# Pro_Trinket_Keyboard_V4_1.net
KiCad netlist of a schematic drawn in EAGLE
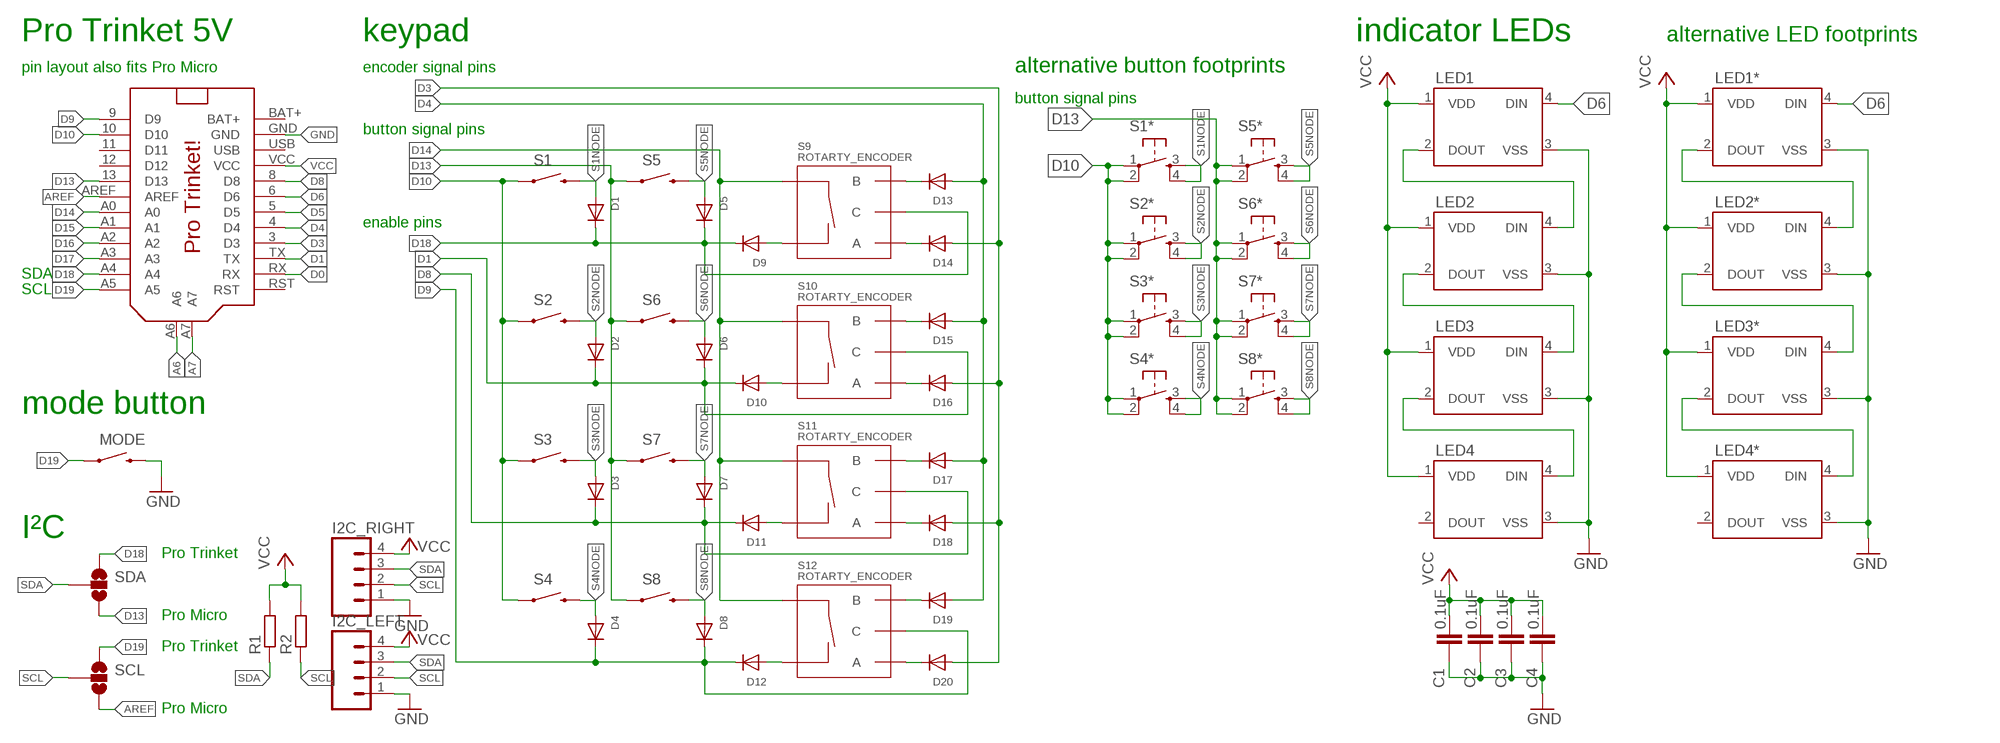
[diagram p0: schematic, sheet 1]

(export (version "E")
  (design (tool "Eeschema 10.0.6"))
  (components
    (comp (ref "C1")
      (value "0.1uF")
      (footprint "eagle-import:0603-CAP")
      (libsource (lib "eagle-import") (part "22PF-50V-5%(0603)"))
    )
    (comp (ref "C2")
      (value "0.1uF")
      (footprint "eagle-import:0603-CAP")
      (libsource (lib "eagle-import") (part "22PF-50V-5%(0603)"))
    )
    (comp (ref "C3")
      (value "0.1uF")
      (footprint "eagle-import:0603-CAP")
      (libsource (lib "eagle-import") (part "22PF-50V-5%(0603)"))
    )
    (comp (ref "C4")
      (value "0.1uF")
      (footprint "eagle-import:0603-CAP")
      (libsource (lib "eagle-import") (part "22PF-50V-5%(0603)"))
    )
    (comp (ref "D1")
      (value "DIODESOD-123")
      (footprint "eagle-import:SOD-123")
      (libsource (lib "eagle-import") (part "DIODESOD-123"))
    )
    (comp (ref "D2")
      (value "DIODESOD-123")
      (footprint "eagle-import:SOD-123")
      (libsource (lib "eagle-import") (part "DIODESOD-123"))
    )
    (comp (ref "D3")
      (value "DIODESOD-123")
      (footprint "eagle-import:SOD-123")
      (libsource (lib "eagle-import") (part "DIODESOD-123"))
    )
    (comp (ref "D4")
      (value "DIODESOD-123")
      (footprint "eagle-import:SOD-123")
      (libsource (lib "eagle-import") (part "DIODESOD-123"))
    )
    (comp (ref "D5")
      (value "DIODESOD-123")
      (footprint "eagle-import:SOD-123")
      (libsource (lib "eagle-import") (part "DIODESOD-123"))
    )
    (comp (ref "D6")
      (value "DIODESOD-123")
      (footprint "eagle-import:SOD-123")
      (libsource (lib "eagle-import") (part "DIODESOD-123"))
    )
    (comp (ref "D7")
      (value "DIODESOD-123")
      (footprint "eagle-import:SOD-123")
      (libsource (lib "eagle-import") (part "DIODESOD-123"))
    )
    (comp (ref "D8")
      (value "DIODESOD-123")
      (footprint "eagle-import:SOD-123")
      (libsource (lib "eagle-import") (part "DIODESOD-123"))
    )
    (comp (ref "D9")
      (value "DIODESOD-123")
      (footprint "eagle-import:SOD-123")
      (libsource (lib "eagle-import") (part "DIODESOD-123"))
    )
    (comp (ref "D10")
      (value "DIODESOD-123")
      (footprint "eagle-import:SOD-123")
      (libsource (lib "eagle-import") (part "DIODESOD-123"))
    )
    (comp (ref "D11")
      (value "DIODESOD-123")
      (footprint "eagle-import:SOD-123")
      (libsource (lib "eagle-import") (part "DIODESOD-123"))
    )
    (comp (ref "D12")
      (value "DIODESOD-123")
      (footprint "eagle-import:SOD-123")
      (libsource (lib "eagle-import") (part "DIODESOD-123"))
    )
    (comp (ref "D13")
      (value "DIODESOD-123")
      (footprint "eagle-import:SOD-123")
      (libsource (lib "eagle-import") (part "DIODESOD-123"))
    )
    (comp (ref "D14")
      (value "DIODESOD-123")
      (footprint "eagle-import:SOD-123")
      (libsource (lib "eagle-import") (part "DIODESOD-123"))
    )
    (comp (ref "D15")
      (value "DIODESOD-123")
      (footprint "eagle-import:SOD-123")
      (libsource (lib "eagle-import") (part "DIODESOD-123"))
    )
    (comp (ref "D16")
      (value "DIODESOD-123")
      (footprint "eagle-import:SOD-123")
      (libsource (lib "eagle-import") (part "DIODESOD-123"))
    )
    (comp (ref "D17")
      (value "DIODESOD-123")
      (footprint "eagle-import:SOD-123")
      (libsource (lib "eagle-import") (part "DIODESOD-123"))
    )
    (comp (ref "D18")
      (value "DIODESOD-123")
      (footprint "eagle-import:SOD-123")
      (libsource (lib "eagle-import") (part "DIODESOD-123"))
    )
    (comp (ref "D19")
      (value "DIODESOD-123")
      (footprint "eagle-import:SOD-123")
      (libsource (lib "eagle-import") (part "DIODESOD-123"))
    )
    (comp (ref "D20")
      (value "DIODESOD-123")
      (footprint "eagle-import:SOD-123")
      (libsource (lib "eagle-import") (part "DIODESOD-123"))
    )
    (comp (ref "I2C_LEFT")
      (value "M04PTH")
      (footprint "eagle-import:1X04")
      (libsource (lib "eagle-import") (part "M04PTH"))
    )
    (comp (ref "I2C_RIGHT")
      (value "M04PTH")
      (footprint "eagle-import:1X04")
      (libsource (lib "eagle-import") (part "M04PTH"))
    )
    (comp (ref "LED1")
      (value "WS2812B")
      (footprint "eagle-import:WS2812B")
      (libsource (lib "eagle-import") (part "WS2812B"))
    )
    (comp (ref "LED1*")
      (value "WS2812B")
      (footprint "eagle-import:WS2812B")
      (libsource (lib "eagle-import") (part "WS2812B"))
    )
    (comp (ref "LED2")
      (value "WS2812B")
      (footprint "eagle-import:WS2812B")
      (libsource (lib "eagle-import") (part "WS2812B"))
    )
    (comp (ref "LED2*")
      (value "WS2812B")
      (footprint "eagle-import:WS2812B")
      (libsource (lib "eagle-import") (part "WS2812B"))
    )
    (comp (ref "LED3")
      (value "WS2812B")
      (footprint "eagle-import:WS2812B")
      (libsource (lib "eagle-import") (part "WS2812B"))
    )
    (comp (ref "LED3*")
      (value "WS2812B")
      (footprint "eagle-import:WS2812B")
      (libsource (lib "eagle-import") (part "WS2812B"))
    )
    (comp (ref "LED4")
      (value "WS2812B")
      (footprint "eagle-import:WS2812B")
      (libsource (lib "eagle-import") (part "WS2812B"))
    )
    (comp (ref "LED4*")
      (value "WS2812B")
      (footprint "eagle-import:WS2812B")
      (libsource (lib "eagle-import") (part "WS2812B"))
    )
    (comp (ref "MODE")
      (value "SWITCH-MOMENTARY-2SIDE_EZ")
      (footprint "eagle-import:TACTILE-PTH-SIDEEZ")
      (libsource (lib "eagle-import") (part "SWITCH-MOMENTARY-2SIDE_EZ"))
    )
    (comp (ref "PRO_TRINKET")
      (value "PRO_TRINKET")
      (footprint "eagle-import:PROTRINKET")
      (libsource (lib "eagle-import") (part "PRO_TRINKET"))
    )
    (comp (ref "R1")
      (value "RESISTORR805-0805")
      (footprint "eagle-import:R805")
      (libsource (lib "eagle-import") (part "RESISTOR-0805R805"))
    )
    (comp (ref "R2")
      (value "RESISTORR805-0805")
      (footprint "eagle-import:R805")
      (libsource (lib "eagle-import") (part "RESISTOR-0805R805"))
    )
    (comp (ref "S1")
      (value "SWITCH-MOMENTARY-212MM")
      (footprint "eagle-import:TACTILE-PTH-12MM")
      (libsource (lib "eagle-import") (part "SWITCH-MOMENTARY-212MM"))
    )
    (comp (ref "S1*")
      (value "TACTILE-SWITCH-PTH")
      (footprint "eagle-import:TAC-SWITCH-PTH")
      (libsource (lib "eagle-import") (part "TACTILE-SWITCH-PTH"))
    )
    (comp (ref "S2")
      (value "SWITCH-MOMENTARY-212MM")
      (footprint "eagle-import:TACTILE-PTH-12MM")
      (libsource (lib "eagle-import") (part "SWITCH-MOMENTARY-212MM"))
    )
    (comp (ref "S2*")
      (value "TACTILE-SWITCH-PTH")
      (footprint "eagle-import:TAC-SWITCH-PTH")
      (libsource (lib "eagle-import") (part "TACTILE-SWITCH-PTH"))
    )
    (comp (ref "S3")
      (value "SWITCH-MOMENTARY-212MM")
      (footprint "eagle-import:TACTILE-PTH-12MM")
      (libsource (lib "eagle-import") (part "SWITCH-MOMENTARY-212MM"))
    )
    (comp (ref "S3*")
      (value "TACTILE-SWITCH-PTH")
      (footprint "eagle-import:TAC-SWITCH-PTH")
      (libsource (lib "eagle-import") (part "TACTILE-SWITCH-PTH"))
    )
    (comp (ref "S4")
      (value "SWITCH-MOMENTARY-212MM")
      (footprint "eagle-import:TACTILE-PTH-12MM")
      (libsource (lib "eagle-import") (part "SWITCH-MOMENTARY-212MM"))
    )
    (comp (ref "S4*")
      (value "TACTILE-SWITCH-PTH")
      (footprint "eagle-import:TAC-SWITCH-PTH")
      (libsource (lib "eagle-import") (part "TACTILE-SWITCH-PTH"))
    )
    (comp (ref "S5")
      (value "SWITCH-MOMENTARY-212MM")
      (footprint "eagle-import:TACTILE-PTH-12MM")
      (libsource (lib "eagle-import") (part "SWITCH-MOMENTARY-212MM"))
    )
    (comp (ref "S5*")
      (value "TACTILE-SWITCH-PTH")
      (footprint "eagle-import:TAC-SWITCH-PTH")
      (libsource (lib "eagle-import") (part "TACTILE-SWITCH-PTH"))
    )
    (comp (ref "S6")
      (value "SWITCH-MOMENTARY-212MM")
      (footprint "eagle-import:TACTILE-PTH-12MM")
      (libsource (lib "eagle-import") (part "SWITCH-MOMENTARY-212MM"))
    )
    (comp (ref "S6*")
      (value "TACTILE-SWITCH-PTH")
      (footprint "eagle-import:TAC-SWITCH-PTH")
      (libsource (lib "eagle-import") (part "TACTILE-SWITCH-PTH"))
    )
    (comp (ref "S7")
      (value "SWITCH-MOMENTARY-212MM")
      (footprint "eagle-import:TACTILE-PTH-12MM")
      (libsource (lib "eagle-import") (part "SWITCH-MOMENTARY-212MM"))
    )
    (comp (ref "S7*")
      (value "TACTILE-SWITCH-PTH")
      (footprint "eagle-import:TAC-SWITCH-PTH")
      (libsource (lib "eagle-import") (part "TACTILE-SWITCH-PTH"))
    )
    (comp (ref "S8")
      (value "SWITCH-MOMENTARY-212MM")
      (footprint "eagle-import:TACTILE-PTH-12MM")
      (libsource (lib "eagle-import") (part "SWITCH-MOMENTARY-212MM"))
    )
    (comp (ref "S8*")
      (value "TACTILE-SWITCH-PTH")
      (footprint "eagle-import:TAC-SWITCH-PTH")
      (libsource (lib "eagle-import") (part "TACTILE-SWITCH-PTH"))
    )
    (comp (ref "S9")
      (value "ROTARTY_ENCODER")
      (footprint "eagle-import:ROTARY_ENC_PLAIN")
      (libsource (lib "eagle-import") (part "ROTARTY_ENCODER"))
    )
    (comp (ref "S10")
      (value "ROTARTY_ENCODER")
      (footprint "eagle-import:ROTARY_ENC_PLAIN")
      (libsource (lib "eagle-import") (part "ROTARTY_ENCODER"))
    )
    (comp (ref "S11")
      (value "ROTARTY_ENCODER")
      (footprint "eagle-import:ROTARY_ENC_PLAIN")
      (libsource (lib "eagle-import") (part "ROTARTY_ENCODER"))
    )
    (comp (ref "S12")
      (value "ROTARTY_ENCODER")
      (footprint "eagle-import:ROTARY_ENC_PLAIN")
      (libsource (lib "eagle-import") (part "ROTARTY_ENCODER"))
    )
    (comp (ref "SCL")
      (value "SOLDERJUMPER_2WAYS")
      (footprint "eagle-import:SJ_3")
      (libsource (lib "eagle-import") (part "SOLDERJUMPER_2WAYS"))
    )
    (comp (ref "SDA")
      (value "SOLDERJUMPER_2WAYS")
      (footprint "eagle-import:SJ_3")
      (libsource (lib "eagle-import") (part "SOLDERJUMPER_2WAYS"))
    )
  )
  (nets
    (net (code "1") (name "/BAT+") (class "Default")
      (node (ref "PRO_TRINKET") (pin "BAT+") (pinfunction "BAT+_BAT+") (pintype "power_in"))
    )
    (net (code "2") (name "/L1NODE") (class "Default")
      (node (ref "LED1") (pin "2") (pinfunction "DOUT_2") (pintype "output"))
      (node (ref "LED1*") (pin "2") (pinfunction "DOUT_2") (pintype "output"))
      (node (ref "LED2") (pin "4") (pinfunction "DIN_4") (pintype "input"))
      (node (ref "LED2*") (pin "4") (pinfunction "DIN_4") (pintype "input"))
    )
    (net (code "3") (name "/L2NODE") (class "Default")
      (node (ref "LED2") (pin "2") (pinfunction "DOUT_2") (pintype "output"))
      (node (ref "LED2*") (pin "2") (pinfunction "DOUT_2") (pintype "output"))
      (node (ref "LED3") (pin "4") (pinfunction "DIN_4") (pintype "input"))
      (node (ref "LED3*") (pin "4") (pinfunction "DIN_4") (pintype "input"))
    )
    (net (code "4") (name "/L3NODE") (class "Default")
      (node (ref "LED3") (pin "2") (pinfunction "DOUT_2") (pintype "output"))
      (node (ref "LED3*") (pin "2") (pinfunction "DOUT_2") (pintype "output"))
      (node (ref "LED4") (pin "4") (pinfunction "DIN_4") (pintype "input"))
      (node (ref "LED4*") (pin "4") (pinfunction "DIN_4") (pintype "input"))
    )
    (net (code "5") (name "/USB") (class "Default")
      (node (ref "PRO_TRINKET") (pin "USB") (pinfunction "USB_USB") (pintype "power_in"))
    )
    (net (code "6") (name "A6") (class "Default")
      (node (ref "PRO_TRINKET") (pin "A6") (pinfunction "A6_A6") (pintype "passive"))
    )
    (net (code "7") (name "A7") (class "Default")
      (node (ref "PRO_TRINKET") (pin "A7") (pinfunction "A7_A7") (pintype "passive"))
    )
    (net (code "8") (name "AREF") (class "Default")
      (node (ref "PRO_TRINKET") (pin "AREF") (pinfunction "AREF_AREF") (pintype "passive"))
      (node (ref "SCL") (pin "3") (pinfunction "3_3") (pintype "passive"))
    )
    (net (code "9") (name "D0") (class "Default")
      (node (ref "PRO_TRINKET") (pin "RX") (pinfunction "RX_RX") (pintype "bidirectional"))
    )
    (net (code "10") (name "D1") (class "Default")
      (node (ref "D10") (pin "C") (pinfunction "C_C") (pintype "passive"))
      (node (ref "D2") (pin "C") (pinfunction "C_C") (pintype "passive"))
      (node (ref "D6") (pin "C") (pinfunction "C_C") (pintype "passive"))
      (node (ref "PRO_TRINKET") (pin "TX") (pinfunction "TX_TX") (pintype "bidirectional"))
      (node (ref "S10") (pin "C") (pinfunction "C_C") (pintype "bidirectional"))
    )
    (net (code "11") (name "D3") (class "Default")
      (node (ref "D14") (pin "A") (pinfunction "A_A") (pintype "passive"))
      (node (ref "D16") (pin "A") (pinfunction "A_A") (pintype "passive"))
      (node (ref "D18") (pin "A") (pinfunction "A_A") (pintype "passive"))
      (node (ref "D20") (pin "A") (pinfunction "A_A") (pintype "passive"))
      (node (ref "PRO_TRINKET") (pin "3") (pinfunction "D3_3") (pintype "bidirectional"))
    )
    (net (code "12") (name "D4") (class "Default")
      (node (ref "D13") (pin "A") (pinfunction "A_A") (pintype "passive"))
      (node (ref "D15") (pin "A") (pinfunction "A_A") (pintype "passive"))
      (node (ref "D17") (pin "A") (pinfunction "A_A") (pintype "passive"))
      (node (ref "D19") (pin "A") (pinfunction "A_A") (pintype "passive"))
      (node (ref "PRO_TRINKET") (pin "4") (pinfunction "D4_4") (pintype "bidirectional"))
    )
    (net (code "13") (name "D5") (class "Default")
      (node (ref "PRO_TRINKET") (pin "5") (pinfunction "D5_5") (pintype "bidirectional"))
    )
    (net (code "14") (name "D6") (class "Default")
      (node (ref "LED1") (pin "4") (pinfunction "DIN_4") (pintype "input"))
      (node (ref "LED1*") (pin "4") (pinfunction "DIN_4") (pintype "input"))
      (node (ref "PRO_TRINKET") (pin "6") (pinfunction "D6_6") (pintype "bidirectional"))
    )
    (net (code "15") (name "D8") (class "Default")
      (node (ref "D11") (pin "C") (pinfunction "C_C") (pintype "passive"))
      (node (ref "D3") (pin "C") (pinfunction "C_C") (pintype "passive"))
      (node (ref "D7") (pin "C") (pinfunction "C_C") (pintype "passive"))
      (node (ref "PRO_TRINKET") (pin "8") (pinfunction "D8_8") (pintype "bidirectional"))
      (node (ref "S11") (pin "C") (pinfunction "C_C") (pintype "bidirectional"))
    )
    (net (code "16") (name "D9") (class "Default")
      (node (ref "D12") (pin "C") (pinfunction "C_C") (pintype "passive"))
      (node (ref "D4") (pin "C") (pinfunction "C_C") (pintype "passive"))
      (node (ref "D8") (pin "C") (pinfunction "C_C") (pintype "passive"))
      (node (ref "PRO_TRINKET") (pin "9") (pinfunction "D9_9") (pintype "bidirectional"))
      (node (ref "S12") (pin "C") (pinfunction "C_C") (pintype "bidirectional"))
    )
    (net (code "17") (name "D10") (class "Default")
      (node (ref "PRO_TRINKET") (pin "10") (pinfunction "D10_10") (pintype "bidirectional"))
      (node (ref "S1") (pin "1") (pinfunction "1_1") (pintype "passive"))
      (node (ref "S1") (pin "2") (pinfunction "1_2") (pintype "passive"))
      (node (ref "S1*") (pin "1") (pinfunction "1_1") (pintype "passive"))
      (node (ref "S1*") (pin "2") (pinfunction "2_2") (pintype "passive"))
      (node (ref "S2") (pin "1") (pinfunction "1_1") (pintype "passive"))
      (node (ref "S2") (pin "2") (pinfunction "1_2") (pintype "passive"))
      (node (ref "S2*") (pin "1") (pinfunction "1_1") (pintype "passive"))
      (node (ref "S2*") (pin "2") (pinfunction "2_2") (pintype "passive"))
      (node (ref "S3") (pin "1") (pinfunction "1_1") (pintype "passive"))
      (node (ref "S3") (pin "2") (pinfunction "1_2") (pintype "passive"))
      (node (ref "S3*") (pin "1") (pinfunction "1_1") (pintype "passive"))
      (node (ref "S3*") (pin "2") (pinfunction "2_2") (pintype "passive"))
      (node (ref "S4") (pin "1") (pinfunction "1_1") (pintype "passive"))
      (node (ref "S4") (pin "2") (pinfunction "1_2") (pintype "passive"))
      (node (ref "S4*") (pin "1") (pinfunction "1_1") (pintype "passive"))
      (node (ref "S4*") (pin "2") (pinfunction "2_2") (pintype "passive"))
    )
    (net (code "18") (name "D13") (class "Default")
      (node (ref "PRO_TRINKET") (pin "13") (pinfunction "D13_13") (pintype "bidirectional"))
      (node (ref "S5") (pin "1") (pinfunction "1_1") (pintype "passive"))
      (node (ref "S5") (pin "2") (pinfunction "1_2") (pintype "passive"))
      (node (ref "S5*") (pin "1") (pinfunction "1_1") (pintype "passive"))
      (node (ref "S5*") (pin "2") (pinfunction "2_2") (pintype "passive"))
      (node (ref "S6") (pin "1") (pinfunction "1_1") (pintype "passive"))
      (node (ref "S6") (pin "2") (pinfunction "1_2") (pintype "passive"))
      (node (ref "S6*") (pin "1") (pinfunction "1_1") (pintype "passive"))
      (node (ref "S6*") (pin "2") (pinfunction "2_2") (pintype "passive"))
      (node (ref "S7") (pin "1") (pinfunction "1_1") (pintype "passive"))
      (node (ref "S7") (pin "2") (pinfunction "1_2") (pintype "passive"))
      (node (ref "S7*") (pin "1") (pinfunction "1_1") (pintype "passive"))
      (node (ref "S7*") (pin "2") (pinfunction "2_2") (pintype "passive"))
      (node (ref "S8") (pin "1") (pinfunction "1_1") (pintype "passive"))
      (node (ref "S8") (pin "2") (pinfunction "1_2") (pintype "passive"))
      (node (ref "S8*") (pin "1") (pinfunction "1_1") (pintype "passive"))
      (node (ref "S8*") (pin "2") (pinfunction "2_2") (pintype "passive"))
      (node (ref "SDA") (pin "3") (pinfunction "3_3") (pintype "passive"))
    )
    (net (code "19") (name "D14") (class "Default")
      (node (ref "PRO_TRINKET") (pin "A0") (pinfunction "A0_A0") (pintype "bidirectional"))
      (node (ref "S10") (pin "SW+") (pinfunction "SW+_SW+") (pintype "bidirectional"))
      (node (ref "S11") (pin "SW+") (pinfunction "SW+_SW+") (pintype "bidirectional"))
      (node (ref "S12") (pin "SW+") (pinfunction "SW+_SW+") (pintype "bidirectional"))
      (node (ref "S9") (pin "SW+") (pinfunction "SW+_SW+") (pintype "bidirectional"))
    )
    (net (code "20") (name "D15") (class "Default")
      (node (ref "PRO_TRINKET") (pin "A1") (pinfunction "A1_A1") (pintype "bidirectional"))
    )
    (net (code "21") (name "D16") (class "Default")
      (node (ref "PRO_TRINKET") (pin "A2") (pinfunction "A2_A2") (pintype "bidirectional"))
    )
    (net (code "22") (name "D17") (class "Default")
      (node (ref "PRO_TRINKET") (pin "A3") (pinfunction "A3_A3") (pintype "bidirectional"))
    )
    (net (code "23") (name "D18") (class "Default")
      (node (ref "D1") (pin "C") (pinfunction "C_C") (pintype "passive"))
      (node (ref "D5") (pin "C") (pinfunction "C_C") (pintype "passive"))
      (node (ref "D9") (pin "C") (pinfunction "C_C") (pintype "passive"))
      (node (ref "PRO_TRINKET") (pin "A4") (pinfunction "A4_A4") (pintype "bidirectional"))
      (node (ref "S9") (pin "C") (pinfunction "C_C") (pintype "bidirectional"))
      (node (ref "SDA") (pin "1") (pinfunction "1_1") (pintype "passive"))
    )
    (net (code "24") (name "D19") (class "Default")
      (node (ref "MODE") (pin "1") (pinfunction "1_1") (pintype "passive"))
      (node (ref "PRO_TRINKET") (pin "A5") (pinfunction "A5_A5") (pintype "bidirectional"))
      (node (ref "SCL") (pin "1") (pinfunction "1_1") (pintype "passive"))
    )
    (net (code "25") (name "GND") (class "Default")
      (node (ref "C1") (pin "1") (pinfunction "1_1") (pintype "passive"))
      (node (ref "C2") (pin "1") (pinfunction "1_1") (pintype "passive"))
      (node (ref "C3") (pin "1") (pinfunction "1_1") (pintype "passive"))
      (node (ref "C4") (pin "1") (pinfunction "1_1") (pintype "passive"))
      (node (ref "I2C_LEFT") (pin "1") (pinfunction "1_1") (pintype "passive"))
      (node (ref "I2C_RIGHT") (pin "1") (pinfunction "1_1") (pintype "passive"))
      (node (ref "LED1") (pin "3") (pinfunction "VSS_3") (pintype "power_in"))
      (node (ref "LED1*") (pin "3") (pinfunction "VSS_3") (pintype "power_in"))
      (node (ref "LED2") (pin "3") (pinfunction "VSS_3") (pintype "power_in"))
      (node (ref "LED2*") (pin "3") (pinfunction "VSS_3") (pintype "power_in"))
      (node (ref "LED3") (pin "3") (pinfunction "VSS_3") (pintype "power_in"))
      (node (ref "LED3*") (pin "3") (pinfunction "VSS_3") (pintype "power_in"))
      (node (ref "LED4") (pin "3") (pinfunction "VSS_3") (pintype "power_in"))
      (node (ref "LED4*") (pin "3") (pinfunction "VSS_3") (pintype "power_in"))
      (node (ref "MODE") (pin "2") (pinfunction "2_2") (pintype "passive"))
      (node (ref "PRO_TRINKET") (pin "GND") (pinfunction "GND_GND") (pintype "power_in"))
    )
    (net (code "26") (name "Net-(D9-PadA)") (class "Default")
      (node (ref "D9") (pin "A") (pinfunction "A_A") (pintype "passive"))
      (node (ref "S9") (pin "SW-") (pinfunction "SW-_SW-") (pintype "bidirectional"))
    )
    (net (code "27") (name "Net-(D10-PadA)") (class "Default")
      (node (ref "D10") (pin "A") (pinfunction "A_A") (pintype "passive"))
      (node (ref "S10") (pin "SW-") (pinfunction "SW-_SW-") (pintype "bidirectional"))
    )
    (net (code "28") (name "Net-(D11-PadA)") (class "Default")
      (node (ref "D11") (pin "A") (pinfunction "A_A") (pintype "passive"))
      (node (ref "S11") (pin "SW-") (pinfunction "SW-_SW-") (pintype "bidirectional"))
    )
    (net (code "29") (name "Net-(D12-PadA)") (class "Default")
      (node (ref "D12") (pin "A") (pinfunction "A_A") (pintype "passive"))
      (node (ref "S12") (pin "SW-") (pinfunction "SW-_SW-") (pintype "bidirectional"))
    )
    (net (code "30") (name "Net-(D13-PadC)") (class "Default")
      (node (ref "D13") (pin "C") (pinfunction "C_C") (pintype "passive"))
      (node (ref "S9") (pin "B") (pinfunction "B_B") (pintype "bidirectional"))
    )
    (net (code "31") (name "Net-(D14-PadC)") (class "Default")
      (node (ref "D14") (pin "C") (pinfunction "C_C") (pintype "passive"))
      (node (ref "S9") (pin "A") (pinfunction "A_A") (pintype "bidirectional"))
    )
    (net (code "32") (name "Net-(D15-PadC)") (class "Default")
      (node (ref "D15") (pin "C") (pinfunction "C_C") (pintype "passive"))
      (node (ref "S10") (pin "B") (pinfunction "B_B") (pintype "bidirectional"))
    )
    (net (code "33") (name "Net-(D16-PadC)") (class "Default")
      (node (ref "D16") (pin "C") (pinfunction "C_C") (pintype "passive"))
      (node (ref "S10") (pin "A") (pinfunction "A_A") (pintype "bidirectional"))
    )
    (net (code "34") (name "Net-(D17-PadC)") (class "Default")
      (node (ref "D17") (pin "C") (pinfunction "C_C") (pintype "passive"))
      (node (ref "S11") (pin "B") (pinfunction "B_B") (pintype "bidirectional"))
    )
    (net (code "35") (name "Net-(D18-PadC)") (class "Default")
      (node (ref "D18") (pin "C") (pinfunction "C_C") (pintype "passive"))
      (node (ref "S11") (pin "A") (pinfunction "A_A") (pintype "bidirectional"))
    )
    (net (code "36") (name "Net-(D19-PadC)") (class "Default")
      (node (ref "D19") (pin "C") (pinfunction "C_C") (pintype "passive"))
      (node (ref "S12") (pin "B") (pinfunction "B_B") (pintype "bidirectional"))
    )
    (net (code "37") (name "Net-(D20-PadC)") (class "Default")
      (node (ref "D20") (pin "C") (pinfunction "C_C") (pintype "passive"))
      (node (ref "S12") (pin "A") (pinfunction "A_A") (pintype "bidirectional"))
    )
    (net (code "38") (name "S1NODE") (class "Default")
      (node (ref "D1") (pin "A") (pinfunction "A_A") (pintype "passive"))
      (node (ref "S1") (pin "3") (pinfunction "2_3") (pintype "passive"))
      (node (ref "S1") (pin "4") (pinfunction "2_4") (pintype "passive"))
      (node (ref "S1*") (pin "3") (pinfunction "3_3") (pintype "passive"))
      (node (ref "S1*") (pin "4") (pinfunction "4_4") (pintype "passive"))
    )
    (net (code "39") (name "S2NODE") (class "Default")
      (node (ref "D2") (pin "A") (pinfunction "A_A") (pintype "passive"))
      (node (ref "S2") (pin "3") (pinfunction "2_3") (pintype "passive"))
      (node (ref "S2") (pin "4") (pinfunction "2_4") (pintype "passive"))
      (node (ref "S2*") (pin "3") (pinfunction "3_3") (pintype "passive"))
      (node (ref "S2*") (pin "4") (pinfunction "4_4") (pintype "passive"))
    )
    (net (code "40") (name "S3NODE") (class "Default")
      (node (ref "D3") (pin "A") (pinfunction "A_A") (pintype "passive"))
      (node (ref "S3") (pin "3") (pinfunction "2_3") (pintype "passive"))
      (node (ref "S3") (pin "4") (pinfunction "2_4") (pintype "passive"))
      (node (ref "S3*") (pin "3") (pinfunction "3_3") (pintype "passive"))
      (node (ref "S3*") (pin "4") (pinfunction "4_4") (pintype "passive"))
    )
    (net (code "41") (name "S4NODE") (class "Default")
      (node (ref "D4") (pin "A") (pinfunction "A_A") (pintype "passive"))
      (node (ref "S4") (pin "3") (pinfunction "2_3") (pintype "passive"))
      (node (ref "S4") (pin "4") (pinfunction "2_4") (pintype "passive"))
      (node (ref "S4*") (pin "3") (pinfunction "3_3") (pintype "passive"))
      (node (ref "S4*") (pin "4") (pinfunction "4_4") (pintype "passive"))
    )
    (net (code "42") (name "S5NODE") (class "Default")
      (node (ref "D5") (pin "A") (pinfunction "A_A") (pintype "passive"))
      (node (ref "S5") (pin "3") (pinfunction "2_3") (pintype "passive"))
      (node (ref "S5") (pin "4") (pinfunction "2_4") (pintype "passive"))
      (node (ref "S5*") (pin "3") (pinfunction "3_3") (pintype "passive"))
      (node (ref "S5*") (pin "4") (pinfunction "4_4") (pintype "passive"))
    )
    (net (code "43") (name "S6NODE") (class "Default")
      (node (ref "D6") (pin "A") (pinfunction "A_A") (pintype "passive"))
      (node (ref "S6") (pin "3") (pinfunction "2_3") (pintype "passive"))
      (node (ref "S6") (pin "4") (pinfunction "2_4") (pintype "passive"))
      (node (ref "S6*") (pin "3") (pinfunction "3_3") (pintype "passive"))
      (node (ref "S6*") (pin "4") (pinfunction "4_4") (pintype "passive"))
    )
    (net (code "44") (name "S7NODE") (class "Default")
      (node (ref "D7") (pin "A") (pinfunction "A_A") (pintype "passive"))
      (node (ref "S7") (pin "3") (pinfunction "2_3") (pintype "passive"))
      (node (ref "S7") (pin "4") (pinfunction "2_4") (pintype "passive"))
      (node (ref "S7*") (pin "3") (pinfunction "3_3") (pintype "passive"))
      (node (ref "S7*") (pin "4") (pinfunction "4_4") (pintype "passive"))
    )
    (net (code "45") (name "S8NODE") (class "Default")
      (node (ref "D8") (pin "A") (pinfunction "A_A") (pintype "passive"))
      (node (ref "S8") (pin "3") (pinfunction "2_3") (pintype "passive"))
      (node (ref "S8") (pin "4") (pinfunction "2_4") (pintype "passive"))
      (node (ref "S8*") (pin "3") (pinfunction "3_3") (pintype "passive"))
      (node (ref "S8*") (pin "4") (pinfunction "4_4") (pintype "passive"))
    )
    (net (code "46") (name "SCL") (class "Default")
      (node (ref "I2C_LEFT") (pin "2") (pinfunction "2_2") (pintype "passive"))
      (node (ref "I2C_RIGHT") (pin "2") (pinfunction "2_2") (pintype "passive"))
      (node (ref "R2") (pin "1") (pinfunction "1_1") (pintype "passive"))
      (node (ref "SCL") (pin "2") (pinfunction "2_2") (pintype "passive"))
    )
    (net (code "47") (name "SDA") (class "Default")
      (node (ref "I2C_LEFT") (pin "3") (pinfunction "3_3") (pintype "passive"))
      (node (ref "I2C_RIGHT") (pin "3") (pinfunction "3_3") (pintype "passive"))
      (node (ref "R1") (pin "1") (pinfunction "1_1") (pintype "passive"))
      (node (ref "SDA") (pin "2") (pinfunction "2_2") (pintype "passive"))
    )
    (net (code "48") (name "VCC") (class "Default")
      (node (ref "C1") (pin "2") (pinfunction "2_2") (pintype "passive"))
      (node (ref "C2") (pin "2") (pinfunction "2_2") (pintype "passive"))
      (node (ref "C3") (pin "2") (pinfunction "2_2") (pintype "passive"))
      (node (ref "C4") (pin "2") (pinfunction "2_2") (pintype "passive"))
      (node (ref "I2C_LEFT") (pin "4") (pinfunction "4_4") (pintype "passive"))
      (node (ref "I2C_RIGHT") (pin "4") (pinfunction "4_4") (pintype "passive"))
      (node (ref "LED1") (pin "1") (pinfunction "VDD_1") (pintype "power_in"))
      (node (ref "LED1*") (pin "1") (pinfunction "VDD_1") (pintype "power_in"))
      (node (ref "LED2") (pin "1") (pinfunction "VDD_1") (pintype "power_in"))
      (node (ref "LED2*") (pin "1") (pinfunction "VDD_1") (pintype "power_in"))
      (node (ref "LED3") (pin "1") (pinfunction "VDD_1") (pintype "power_in"))
      (node (ref "LED3*") (pin "1") (pinfunction "VDD_1") (pintype "power_in"))
      (node (ref "LED4") (pin "1") (pinfunction "VDD_1") (pintype "power_in"))
      (node (ref "LED4*") (pin "1") (pinfunction "VDD_1") (pintype "power_in"))
      (node (ref "PRO_TRINKET") (pin "VCC") (pinfunction "VCC_VCC") (pintype "power_in"))
      (node (ref "R1") (pin "2") (pinfunction "2_2") (pintype "passive"))
      (node (ref "R2") (pin "2") (pinfunction "2_2") (pintype "passive"))
    )
    (net (code "49") (name "unconnected-(LED4*-DOUT-Pad2)") (class "Default")
      (node (ref "LED4*") (pin "2") (pinfunction "DOUT_2") (pintype "output"))
    )
    (net (code "50") (name "unconnected-(LED4-DOUT-Pad2)") (class "Default")
      (node (ref "LED4") (pin "2") (pinfunction "DOUT_2") (pintype "output"))
    )
    (net (code "51") (name "unconnected-(PRO_TRINKET-D11-Pad11)") (class "Default")
      (node (ref "PRO_TRINKET") (pin "11") (pinfunction "D11_11") (pintype "bidirectional"))
    )
    (net (code "52") (name "unconnected-(PRO_TRINKET-D12-Pad12)") (class "Default")
      (node (ref "PRO_TRINKET") (pin "12") (pinfunction "D12_12") (pintype "bidirectional"))
    )
    (net (code "53") (name "unconnected-(PRO_TRINKET-PadRST)") (class "Default")
      (node (ref "PRO_TRINKET") (pin "RST") (pinfunction "RST_RST") (pintype "passive"))
    )
  )
)
